# ADC.net
KiCad netlist of a schematic drawn in Altium Designer
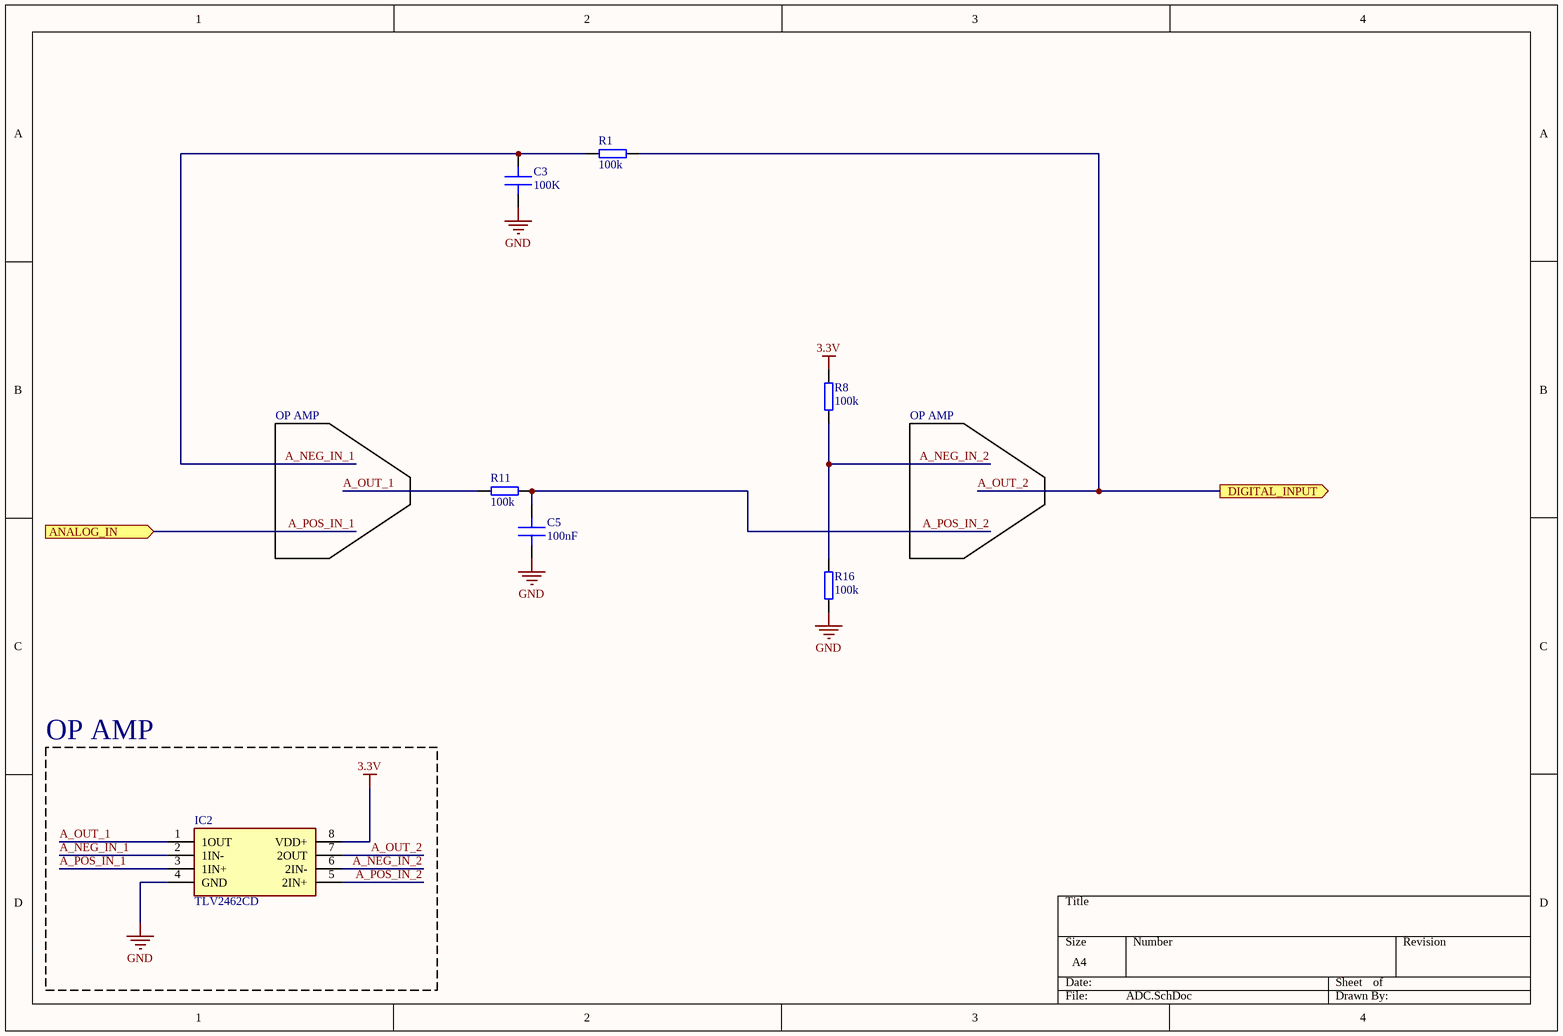
[diagram p0: ADC.SchDoc]

(export (version "E")
  (design (tool "Eeschema 10.0.6"))
  (components
    (comp (ref "C3")
      (value "100K")
      (footprint "C 0402")
      (description "MLCC Capacitor")
      (libsource (lib "sigma-delta-adc-uart") (part "Capacitor"))
    )
    (comp (ref "C5")
      (value "100nF")
      (footprint "C 0402")
      (description "MLCC Capacitor")
      (libsource (lib "sigma-delta-adc-uart") (part "Capacitor"))
    )
    (comp (ref "IC2")
      (value "TLV2462CD")
      (footprint "SamacSys:SOIC127P600X175-8N")
      (description "Integrated Circuit")
      (fields (field (name "MOUSER PART NUMBER") "595-TLV2462CD"))
      (libsource (lib "*") (part "TLV2462CD"))
    )
    (comp (ref "R1")
      (value "100k")
      (footprint "R 0402")
      (description "General pourpouse resistor")
      (libsource (lib "sigma-delta-adc-uart") (part "Resistor"))
    )
    (comp (ref "R8")
      (value "100k")
      (footprint "R 0402")
      (description "General pourpouse resistor")
      (libsource (lib "sigma-delta-adc-uart") (part "Resistor"))
    )
    (comp (ref "R11")
      (value "100k")
      (footprint "R 0402")
      (description "General pourpouse resistor")
      (libsource (lib "sigma-delta-adc-uart") (part "Resistor"))
    )
    (comp (ref "R16")
      (value "100k")
      (footprint "R 0402")
      (description "General pourpouse resistor")
      (libsource (lib "sigma-delta-adc-uart") (part "Resistor"))
    )
  )
  (nets
    (net (code "1") (name "/A_NEG_IN_1") (class "Default")
      (node (ref "C3") (pin "1") (pinfunction "1_1") (pintype "passive"))
      (node (ref "IC2") (pin "2") (pinfunction "1IN-_2") (pintype "passive"))
      (node (ref "R1") (pin "2") (pinfunction "2_2") (pintype "passive"))
    )
    (net (code "2") (name "/A_NEG_IN_2") (class "Default")
      (node (ref "IC2") (pin "6") (pinfunction "2IN-_6") (pintype "passive"))
      (node (ref "R16") (pin "1") (pinfunction "1_1") (pintype "passive"))
      (node (ref "R8") (pin "2") (pinfunction "2_2") (pintype "passive"))
    )
    (net (code "3") (name "/A_OUT_1") (class "Default")
      (node (ref "IC2") (pin "1") (pinfunction "1OUT_1") (pintype "passive"))
      (node (ref "R11") (pin "2") (pinfunction "2_2") (pintype "passive"))
    )
    (net (code "4") (name "/A_OUT_2") (class "Default")
      (node (ref "IC2") (pin "7") (pinfunction "2OUT_7") (pintype "passive"))
      (node (ref "R1") (pin "1") (pinfunction "1_1") (pintype "passive"))
    )
    (net (code "5") (name "/A_POS_IN_1") (class "Default")
      (node (ref "IC2") (pin "3") (pinfunction "1IN+_3") (pintype "passive"))
    )
    (net (code "6") (name "/A_POS_IN_2") (class "Default")
      (node (ref "C5") (pin "1") (pinfunction "1_1") (pintype "passive"))
      (node (ref "IC2") (pin "5") (pinfunction "2IN+_5") (pintype "passive"))
      (node (ref "R11") (pin "1") (pinfunction "1_1") (pintype "passive"))
    )
    (net (code "7") (name "3.3V") (class "Default")
      (node (ref "IC2") (pin "8") (pinfunction "VDD+_8") (pintype "passive"))
      (node (ref "R8") (pin "1") (pinfunction "1_1") (pintype "passive"))
    )
    (net (code "8") (name "GND") (class "Default")
      (node (ref "C3") (pin "2") (pinfunction "2_2") (pintype "passive"))
      (node (ref "C5") (pin "2") (pinfunction "2_2") (pintype "passive"))
      (node (ref "IC2") (pin "4") (pinfunction "GND_4") (pintype "passive"))
      (node (ref "R16") (pin "2") (pinfunction "2_2") (pintype "passive"))
    )
  )
)
